# Pressure_Sensor.net
KiCad netlist of a schematic drawn in Altium Designer
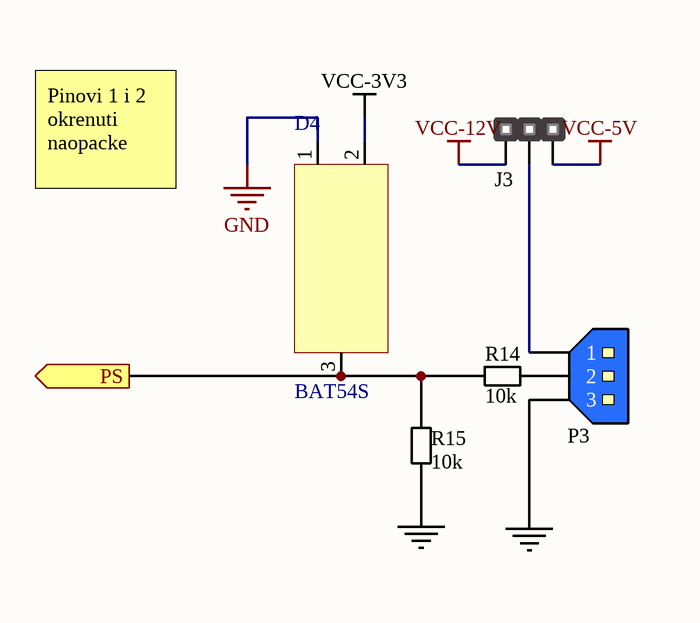
[diagram p0: Pressure_Sensor.SchDoc]

(export (version "E")
  (design (tool "Eeschema 10.0.6"))
  (components
    (comp (ref "D4")
      (value "BAT54S")
      (footprint "BAT54S")
      (libsource (lib "Discrete_Semiconductor") (part "BAT54S"))
    )
    (comp (ref "J3")
      (value "*")
      (footprint "HM1X3")
      (libsource (lib "Electro_Mechanical") (part "HEADER_1x3"))
    )
    (comp (ref "P3")
      (value "TE CONNECTIVITY_3PIN_MALE")
      (footprint "TE CONNECTIVITY_3PIN_MALE")
      (description "BLUE_3PIN_CONECTOR")
      (fields (field (name "MANUFACTURER") "TE CONNECTIVITY / AMP"))
      (libsource (lib "Electro_Mechanical") (part "TE CONNECTIVITY_3PIN_MALE"))
    )
    (comp (ref "R14")
      (value "10k")
      (footprint "RESC2013X38N-0805-NOOVERLAY")
      (description "RES SMD 10 kOhm 1/8W 0805")
      (libsource (lib "") (part "000001002_1"))
    )
    (comp (ref "R15")
      (value "10k")
      (footprint "RESC2013X38N-0805-NOOVERLAY")
      (description "RES SMD 10 kOhm 1/8W 0805")
      (libsource (lib "Resistors") (part "000001002"))
    )
  )
  (nets
    (net (code "1") (name "/PS") (class "Default")
      (node (ref "D4") (pin "3") (pinfunction "3_3") (pintype "passive"))
      (node (ref "R14") (pin "2") (pinfunction "2_2") (pintype "passive"))
      (node (ref "R15") (pin "2") (pinfunction "2_2") (pintype "passive"))
    )
    (net (code "2") (name "GND") (class "Default")
      (node (ref "P3") (pin "3") (pinfunction "3_3") (pintype "passive"))
      (node (ref "R15") (pin "1") (pinfunction "1_1") (pintype "passive"))
    )
    (net (code "3") (name "Net-(J3-Pad2)") (class "Default")
      (node (ref "J3") (pin "2") (pinfunction "2_2") (pintype "passive"))
      (node (ref "P3") (pin "1") (pinfunction "1_1") (pintype "passive"))
    )
    (net (code "4") (name "Net-(P3-Pad2)") (class "Default")
      (node (ref "P3") (pin "2") (pinfunction "2_2") (pintype "passive"))
      (node (ref "R14") (pin "1") (pinfunction "1_1") (pintype "passive"))
    )
    (net (code "6") (name "VCC-5V") (class "Default")
      (node (ref "J3") (pin "3") (pinfunction "3_3") (pintype "passive"))
    )
    (net (code "7") (name "VCC-12V") (class "Default")
      (node (ref "J3") (pin "1") (pinfunction "1_1") (pintype "passive"))
    )
    (net (code "8") (name "unconnected-(D4-Pad1)") (class "Default")
      (node (ref "D4") (pin "1") (pinfunction "1_1") (pintype "passive"))
    )
    (net (code "9") (name "unconnected-(D4-Pad2)") (class "Default")
      (node (ref "D4") (pin "2") (pinfunction "2_2") (pintype "passive"))
    )
  )
)
